# Power_Supply.net
KiCad netlist of a schematic drawn in Altium Designer
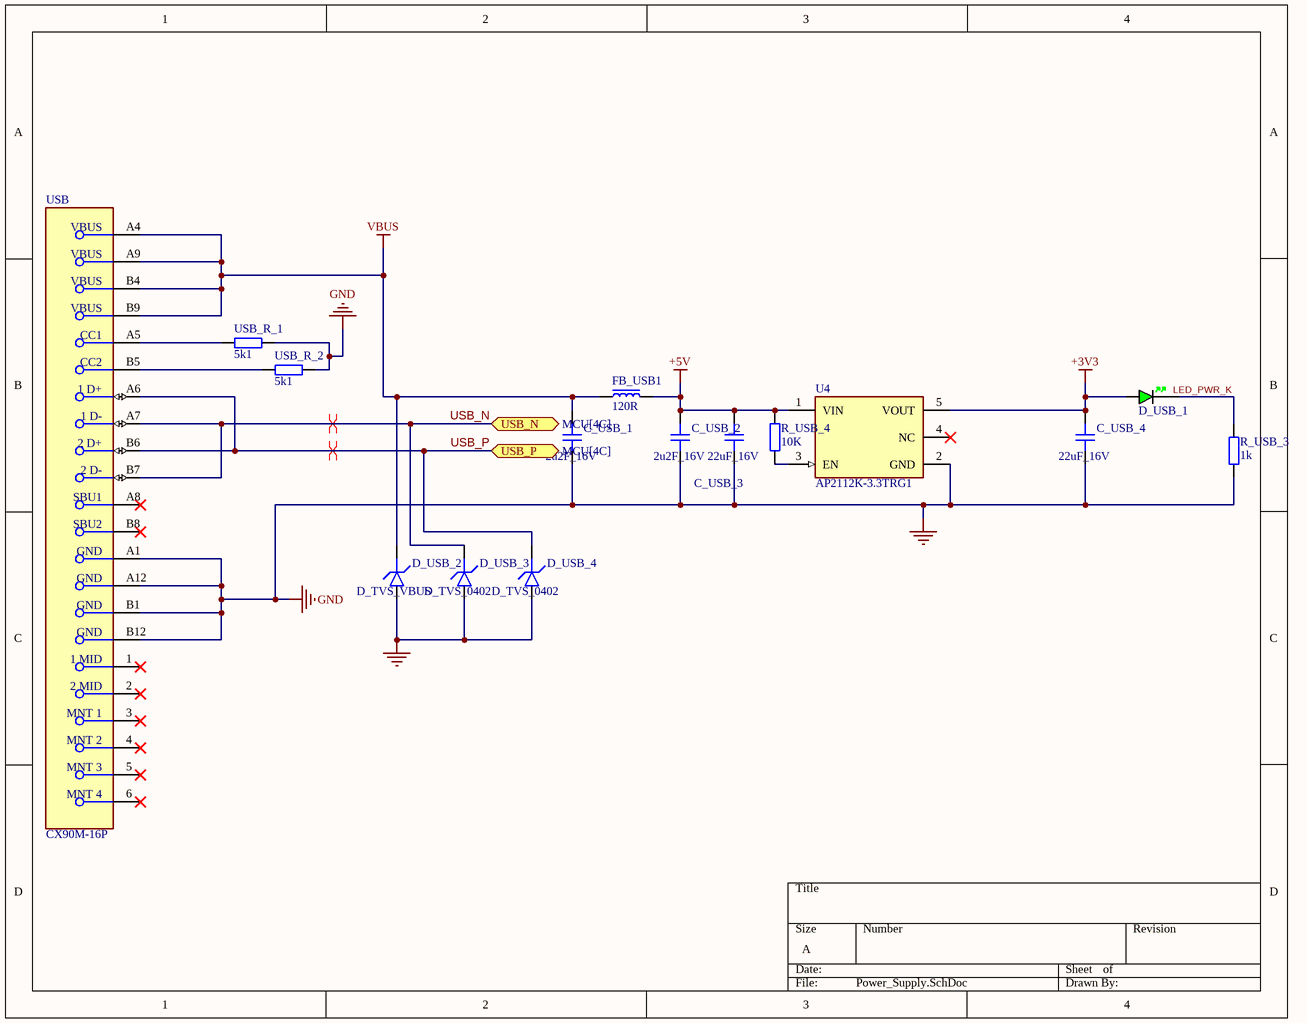
[diagram p0: Power_Supply.SchDoc]

(export (version "E")
  (design (tool "Eeschema 10.0.6"))
  (components
    (comp (ref "C_USB_1")
      (value "2u2F_16V")
      (footprint "CAP_0603")
      (description "Capacitor SMD 0603")
      (libsource (lib "Schematic-Lib-PhilsLab") (part "CAP_0603"))
    )
    (comp (ref "C_USB_2")
      (value "2u2F_16V")
      (footprint "CAP_0603")
      (description "Capacitor SMD 0603")
      (libsource (lib "Schematic-Lib-PhilsLab") (part "CAP_0603"))
    )
    (comp (ref "C_USB_3")
      (value "22uF_16V")
      (footprint "CAP_0805")
      (description "Capacitor SMD 0805")
      (libsource (lib "Schematic-Lib-PhilsLab") (part "CAP_0805"))
    )
    (comp (ref "C_USB_4")
      (value "22uF_16V")
      (footprint "CAP_0805")
      (description "Capacitor SMD 0805")
      (libsource (lib "Schematic-Lib-PhilsLab") (part "CAP_0805"))
    )
    (comp (ref "D_USB_1")
      (value "GREEN")
      (footprint "LED_0402_GREEN")
      (description "LED 0402 GREEN SMD")
      (libsource (lib "Schematic-Lib-PhilsLab") (part "LED_0402_GREEN"))
    )
    (comp (ref "D_USB_2")
      (value "D_TVS_VBUS")
      (footprint "D_0402")
      (description "Diode TVS / ESD 0402")
      (libsource (lib "Schematic-Lib-PhilsLab") (part "D_TVS_0402"))
    )
    (comp (ref "D_USB_3")
      (value "D_TVS_0402")
      (footprint "D_0402")
      (description "Diode TVS / ESD 0402")
      (libsource (lib "Schematic-Lib-PhilsLab") (part "D_TVS_0402"))
    )
    (comp (ref "D_USB_4")
      (value "D_TVS_0402")
      (footprint "D_0402")
      (description "Diode TVS / ESD 0402")
      (libsource (lib "Schematic-Lib-PhilsLab") (part "D_TVS_0402"))
    )
    (comp (ref "FB_USB1")
      (value "120R")
      (footprint "FB_0603")
      (description "Ferrite Bead SMD 0603")
      (libsource (lib "Schematic-Lib-PhilsLab") (part "FB_0603"))
    )
    (comp (ref "R_USB_3")
      (value "1k")
      (footprint "RES_0402")
      (description "Resistor SMD 0402")
      (libsource (lib "Schematic-Lib-PhilsLab") (part "RES_0402"))
    )
    (comp (ref "R_USB_4")
      (value "10K")
      (footprint "RES_0402")
      (description "Resistor SMD 0402")
      (libsource (lib "Schematic-Lib-PhilsLab") (part "RES_0402"))
    )
    (comp (ref "U4")
      (value "AP2112K-3.3TRG1")
      (footprint "FP-SOT25-IPC_A")
      (description "IC REG LINEAR 3.3V 600MA SOT25")
      (libsource (lib "Altium Content Vault") (part "c8ab751aee5229183125ab046a11caa"))
    )
    (comp (ref "USB")
      (value "CX90M-16P")
      (footprint "FP-CX90M-16P-MFG")
      (description "CONN RCPT USB2.0 TYPEC 16POS SMD")
      (libsource (lib "Altium Content Vault") (part "6b7e9819a715c2d1d3babe584a73dea"))
    )
    (comp (ref "USB_R_1")
      (value "5k1")
      (footprint "RES_0402")
      (description "Resistor SMD 0402")
      (libsource (lib "Schematic-Lib-PhilsLab") (part "RES_0402"))
    )
    (comp (ref "USB_R_2")
      (value "5k1")
      (footprint "RES_0402")
      (description "Resistor SMD 0402")
      (libsource (lib "Schematic-Lib-PhilsLab") (part "RES_0402"))
    )
  )
  (nets
    (net (code "1") (name "+3V3") (class "Default")
      (node (ref "C_USB_4") (pin "2") (pinfunction "2_2") (pintype "passive"))
      (node (ref "D_USB_1") (pin "A") (pinfunction "A_A") (pintype "passive"))
      (node (ref "U4") (pin "5") (pinfunction "VOUT_5") (pintype "power_in"))
    )
    (net (code "2") (name "+5V") (class "Default")
      (node (ref "C_USB_2") (pin "2") (pinfunction "2_2") (pintype "passive"))
      (node (ref "C_USB_3") (pin "2") (pinfunction "2_2") (pintype "passive"))
      (node (ref "FB_USB1") (pin "2") (pinfunction "2_2") (pintype "passive"))
      (node (ref "R_USB_4") (pin "1") (pinfunction "1_1") (pintype "passive"))
      (node (ref "U4") (pin "1") (pinfunction "VIN_1") (pintype "power_in"))
    )
    (net (code "3") (name "/LED_PWR_K") (class "Default")
      (node (ref "D_USB_1") (pin "K") (pinfunction "K_K") (pintype "passive"))
      (node (ref "R_USB_3") (pin "2") (pinfunction "2_2") (pintype "passive"))
    )
    (net (code "4") (name "/USB_N") (class "Default")
      (node (ref "D_USB_3") (pin "K") (pinfunction "K_K") (pintype "passive"))
      (node (ref "USB") (pin "A7") (pinfunction "1_D-_A7") (pintype "bidirectional"))
      (node (ref "USB") (pin "B7") (pinfunction "2_D-_B7") (pintype "bidirectional"))
    )
    (net (code "5") (name "/USB_P") (class "Default")
      (node (ref "D_USB_4") (pin "K") (pinfunction "K_K") (pintype "passive"))
      (node (ref "USB") (pin "A6") (pinfunction "1_D+_A6") (pintype "bidirectional"))
      (node (ref "USB") (pin "B6") (pinfunction "2_D+_B6") (pintype "bidirectional"))
    )
    (net (code "6") (name "GND") (class "Default")
      (node (ref "C_USB_1") (pin "1") (pinfunction "1_1") (pintype "passive"))
      (node (ref "C_USB_2") (pin "1") (pinfunction "1_1") (pintype "passive"))
      (node (ref "C_USB_3") (pin "1") (pinfunction "1_1") (pintype "passive"))
      (node (ref "C_USB_4") (pin "1") (pinfunction "1_1") (pintype "passive"))
      (node (ref "D_USB_2") (pin "A") (pinfunction "A_A") (pintype "passive"))
      (node (ref "D_USB_3") (pin "A") (pinfunction "A_A") (pintype "passive"))
      (node (ref "D_USB_4") (pin "A") (pinfunction "A_A") (pintype "passive"))
      (node (ref "R_USB_3") (pin "1") (pinfunction "1_1") (pintype "passive"))
      (node (ref "U4") (pin "2") (pinfunction "GND_2") (pintype "power_in"))
      (node (ref "USB") (pin "A1") (pinfunction "GND_A1") (pintype "power_in"))
      (node (ref "USB") (pin "A12") (pinfunction "GND_A12") (pintype "power_in"))
      (node (ref "USB") (pin "B1") (pinfunction "GND_B1") (pintype "power_in"))
      (node (ref "USB") (pin "B12") (pinfunction "GND_B12") (pintype "power_in"))
      (node (ref "USB_R_1") (pin "2") (pinfunction "2_2") (pintype "passive"))
      (node (ref "USB_R_2") (pin "2") (pinfunction "2_2") (pintype "passive"))
    )
    (net (code "7") (name "Net-(U4-EN)") (class "Default")
      (node (ref "R_USB_4") (pin "2") (pinfunction "2_2") (pintype "passive"))
      (node (ref "U4") (pin "3") (pinfunction "EN_3") (pintype "input"))
    )
    (net (code "8") (name "Net-(USB-CC1)") (class "Default")
      (node (ref "USB") (pin "A5") (pinfunction "CC1_A5") (pintype "passive"))
      (node (ref "USB_R_1") (pin "1") (pinfunction "1_1") (pintype "passive"))
    )
    (net (code "9") (name "Net-(USB-CC2)") (class "Default")
      (node (ref "USB") (pin "B5") (pinfunction "CC2_B5") (pintype "passive"))
      (node (ref "USB_R_2") (pin "1") (pinfunction "1_1") (pintype "passive"))
    )
    (net (code "10") (name "VBUS") (class "Default")
      (node (ref "C_USB_1") (pin "2") (pinfunction "2_2") (pintype "passive"))
      (node (ref "D_USB_2") (pin "K") (pinfunction "K_K") (pintype "passive"))
      (node (ref "FB_USB1") (pin "1") (pinfunction "1_1") (pintype "passive"))
      (node (ref "USB") (pin "A4") (pinfunction "VBUS_A4") (pintype "power_in"))
      (node (ref "USB") (pin "A9") (pinfunction "VBUS_A9") (pintype "power_in"))
      (node (ref "USB") (pin "B4") (pinfunction "VBUS_B4") (pintype "power_in"))
      (node (ref "USB") (pin "B9") (pinfunction "VBUS_B9") (pintype "power_in"))
    )
    (net (code "11") (name "unconnected-(U4-NC-Pad4)") (class "Default")
      (node (ref "U4") (pin "4") (pinfunction "NC_4") (pintype "passive+no_connect"))
    )
    (net (code "12") (name "unconnected-(USB-1_MID-Pad1)") (class "Default")
      (node (ref "USB") (pin "1") (pinfunction "1_MID_1") (pintype "passive+no_connect"))
    )
    (net (code "13") (name "unconnected-(USB-2_MID-Pad2)") (class "Default")
      (node (ref "USB") (pin "2") (pinfunction "2_MID_2") (pintype "passive+no_connect"))
    )
    (net (code "14") (name "unconnected-(USB-MNT_1-Pad3)") (class "Default")
      (node (ref "USB") (pin "3") (pinfunction "MNT_1_3") (pintype "passive+no_connect"))
    )
    (net (code "15") (name "unconnected-(USB-MNT_2-Pad4)") (class "Default")
      (node (ref "USB") (pin "4") (pinfunction "MNT_2_4") (pintype "passive+no_connect"))
    )
    (net (code "16") (name "unconnected-(USB-MNT_3-Pad5)") (class "Default")
      (node (ref "USB") (pin "5") (pinfunction "MNT_3_5") (pintype "passive+no_connect"))
    )
    (net (code "17") (name "unconnected-(USB-MNT_4-Pad6)") (class "Default")
      (node (ref "USB") (pin "6") (pinfunction "MNT_4_6") (pintype "passive+no_connect"))
    )
    (net (code "18") (name "unconnected-(USB-SBU1-PadA8)") (class "Default")
      (node (ref "USB") (pin "A8") (pinfunction "SBU1_A8") (pintype "passive+no_connect"))
    )
    (net (code "19") (name "unconnected-(USB-SBU2-PadB8)") (class "Default")
      (node (ref "USB") (pin "B8") (pinfunction "SBU2_B8") (pintype "passive+no_connect"))
    )
  )
)
